# MCU.net
KiCad netlist of a schematic drawn in Altium Designer
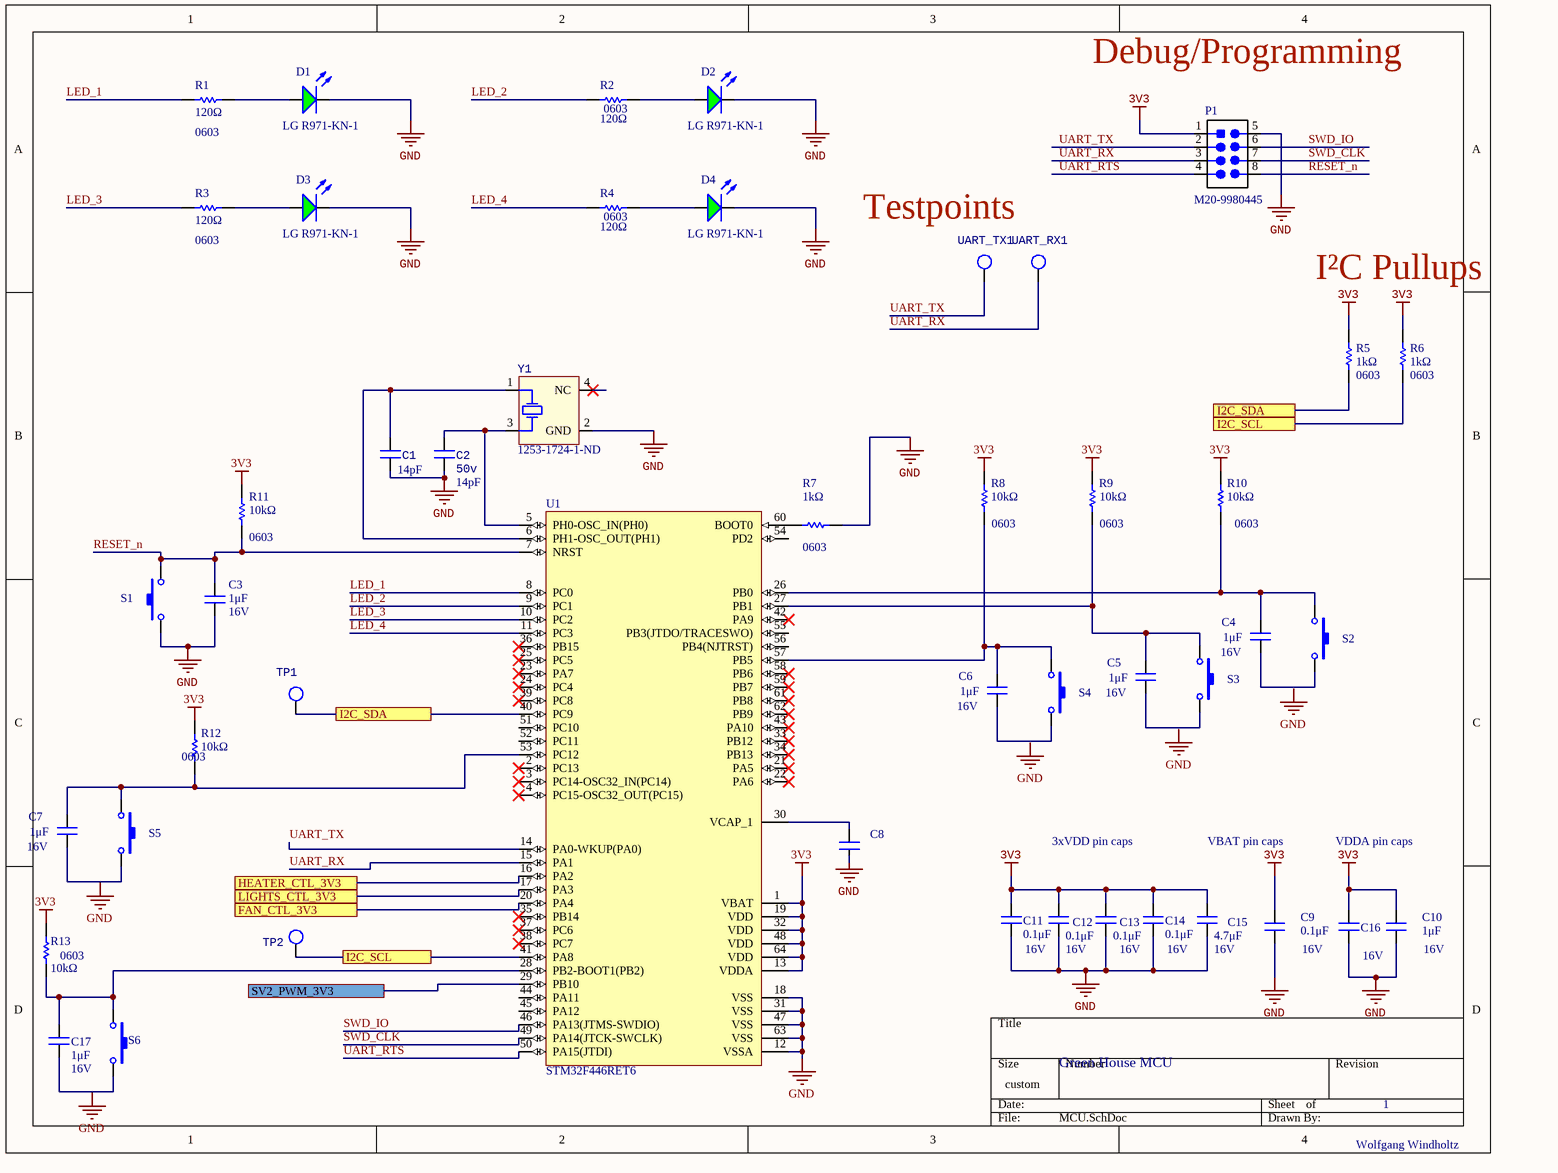
[diagram p0: MCU.SchDoc]

(export (version "E")
  (design (tool "Eeschema 10.0.6"))
  (components
    (comp (ref "C1")
      (value "14pF")
      (footprint "CAP0603")
      (description "CAP CER 14PF 50V C0G/NP0 0603")
      (fields (field (name "Comment") "CAP_14pF_50V_0603"))
      (libsource (lib "UWRT_Schematic_Library_2020") (part "CAP_14pF_50V_0603"))
    )
    (comp (ref "C2")
      (value "50v")
      (footprint "CAP0603")
      (description "CAP CER 14PF 50V C0G/NP0 0603")
      (fields (field (name "ALTIUM_VALUE") "14pF"))
      (libsource (lib "UWRT_Schematic_Library_2020") (part "CAP_14pF_50V_0603"))
    )
    (comp (ref "C3")
      (value "1μF")
      (footprint "CAP2012")
      (description "CAP CER 1UF 16V X7R 0805")
      (fields (field (name "VOLTAGE RATING") "16V") (field (name "Comment") "CAP_1uF_16V_0805"))
      (libsource (lib "UWRT_Schematic_Library_2020") (part "CAP_1uF_16V_0805"))
    )
    (comp (ref "C4")
      (value "1μF")
      (footprint "CAP2012")
      (description "CAP CER 1UF 16V X7R 0805")
      (fields (field (name "VOLTAGE RATING") "16V") (field (name "Comment") "CAP_1uF_16V_0805"))
      (libsource (lib "UWRT_Schematic_Library_2020") (part "CAP_1uF_16V_0805"))
    )
    (comp (ref "C5")
      (value "1μF")
      (footprint "CAP2012")
      (description "CAP CER 1UF 16V X7R 0805")
      (fields (field (name "VOLTAGE RATING") "16V") (field (name "Comment") "CAP_1uF_16V_0805"))
      (libsource (lib "UWRT_Schematic_Library_2020") (part "CAP_1uF_16V_0805"))
    )
    (comp (ref "C6")
      (value "1μF")
      (footprint "CAP2012")
      (description "CAP CER 1UF 16V X7R 0805")
      (fields (field (name "VOLTAGE RATING") "16V") (field (name "Comment") "CAP_1uF_16V_0805"))
      (libsource (lib "UWRT_Schematic_Library_2020") (part "CAP_1uF_16V_0805"))
    )
    (comp (ref "C7")
      (value "1μF")
      (footprint "CAP2012")
      (description "CAP CER 1UF 16V X7R 0805")
      (fields (field (name "VOLTAGE RATING") "16V") (field (name "Comment") "CAP_1uF_16V_0805"))
      (libsource (lib "UWRT_Schematic_Library_2020") (part "CAP_1uF_16V_0805"))
    )
    (comp (ref "C8")
      (value "CAP_4.7uF_50V_1206")
      (footprint "CAP1206")
      (description "CAP CER 4.7UF 50V X7R 1206")
      (libsource (lib "UWRT_Schematic_Library_2020") (part "CAP_4.7uF_50V_1206"))
    )
    (comp (ref "C9")
      (value "0.1μF")
      (footprint "CAP0603")
      (description "CAP CER 0.1UF 16V X7R 0603")
      (fields (field (name "VOLTAGE RATING") "16V") (field (name "Comment") "CAP_0.1uF_16V_0603"))
      (libsource (lib "UWRT_Schematic_Library_2020") (part "CAP_0.1uF_16V_0603"))
    )
    (comp (ref "C10")
      (value "1μF")
      (footprint "CAP0603")
      (description "CAP CER 1UF 16V Y5V 0603")
      (fields (field (name "VOLTAGE RATING") "16V") (field (name "Comment") "CAP_1uF_16V_0603"))
      (libsource (lib "UWRT_Schematic_Library_2020") (part "CAP_1uF_16V_0603"))
    )
    (comp (ref "C11")
      (value "0.1μF")
      (footprint "CAP0603")
      (description "CAP CER 0.1UF 16V X7R 0603")
      (fields (field (name "VOLTAGE RATING") "16V") (field (name "Comment") "CAP_0.1uF_16V_0603"))
      (libsource (lib "UWRT_Schematic_Library_2020") (part "CAP_0.1uF_16V_0603"))
    )
    (comp (ref "C12")
      (value "0.1μF")
      (footprint "CAP0603")
      (description "CAP CER 0.1UF 16V X7R 0603")
      (fields (field (name "VOLTAGE RATING") "16V") (field (name "Comment") "CAP_0.1uF_16V_0603"))
      (libsource (lib "UWRT_Schematic_Library_2020") (part "CAP_0.1uF_16V_0603"))
    )
    (comp (ref "C13")
      (value "0.1μF")
      (footprint "CAP0603")
      (description "CAP CER 0.1UF 16V X7R 0603")
      (fields (field (name "VOLTAGE RATING") "16V") (field (name "Comment") "CAP_0.1uF_16V_0603"))
      (libsource (lib "UWRT_Schematic_Library_2020") (part "CAP_0.1uF_16V_0603"))
    )
    (comp (ref "C14")
      (value "0.1μF")
      (footprint "CAP0603")
      (description "CAP CER 0.1UF 16V X7R 0603")
      (fields (field (name "VOLTAGE RATING") "16V") (field (name "Comment") "CAP_0.1uF_16V_0603"))
      (libsource (lib "UWRT_Schematic_Library_2020") (part "CAP_0.1uF_16V_0603"))
    )
    (comp (ref "C15")
      (value "4.7μF")
      (footprint "CAP0603")
      (description "CAP CER 4.7UF 16V X6S 0603")
      (fields (field (name "VOLTAGE RATING") "16V") (field (name "Comment") "CAP_4.7uF_16V_0603"))
      (libsource (lib "UWRT_Schematic_Library_2020") (part "CAP_4.7uF_16V_0603"))
    )
    (comp (ref "C16")
      (value "CAP_10nF_16V_0805")
      (footprint "CAP2012")
      (description "CAP CER 10000PF 16V X7R 0805")
      (fields (field (name "VOLTAGE RATING") "16V"))
      (libsource (lib "UWRT_Schematic_Library_2020") (part "CAP_10nF_16V_0805"))
    )
    (comp (ref "C17")
      (value "1μF")
      (footprint "CAP2012")
      (description "CAP CER 1UF 16V X7R 0805")
      (fields (field (name "VOLTAGE RATING") "16V") (field (name "Comment") "CAP_1uF_16V_0805"))
      (libsource (lib "UWRT_Schematic_Library_2020") (part "CAP_1uF_16V_0805"))
    )
    (comp (ref "D1")
      (value "LED_GREEN")
      (footprint "LED_0805_GREEN")
      (description "LED GREEN DIFFUSED 0805 SMD")
      (fields (field (name "MANUFACTURER PART NUMBER 1") "LG R971-KN-1"))
      (libsource (lib "UWRT_Schematic_Library_2020") (part "LED_GREEN"))
    )
    (comp (ref "D2")
      (value "LED_GREEN")
      (footprint "LED_0805_GREEN")
      (description "LED GREEN DIFFUSED 0805 SMD")
      (fields (field (name "MANUFACTURER PART NUMBER 1") "LG R971-KN-1"))
      (libsource (lib "UWRT_Schematic_Library_2020") (part "LED_GREEN"))
    )
    (comp (ref "D3")
      (value "LED_GREEN")
      (footprint "LED_0805_GREEN")
      (description "LED GREEN DIFFUSED 0805 SMD")
      (fields (field (name "MANUFACTURER PART NUMBER 1") "LG R971-KN-1"))
      (libsource (lib "UWRT_Schematic_Library_2020") (part "LED_GREEN"))
    )
    (comp (ref "D4")
      (value "LED_GREEN")
      (footprint "LED_0805_GREEN")
      (description "LED GREEN DIFFUSED 0805 SMD")
      (fields (field (name "MANUFACTURER PART NUMBER 1") "LG R971-KN-1"))
      (libsource (lib "UWRT_Schematic_Library_2020") (part "LED_GREEN"))
    )
    (comp (ref "P1")
      (value "HEADER 4X2")
      (footprint "HEADER_2X4")
      (description "CONN HEADER VERT 8POS 2.54MM")
      (fields (field (name "MANUFACTURER PART NUMBER 1") "M20-9980445"))
      (libsource (lib "UWRT_Schematic_Library_2020") (part "HEADER 4X2"))
    )
    (comp (ref "R1")
      (value "120Ω")
      (footprint "RESC0603")
      (description "RES 120 OHM 5% 1/10W 0603")
      (fields (field (name "PACKAGE/FOOTPRINT") "0603") (field (name "Comment") "RES_120Ω_0603_5%"))
      (libsource (lib "UWRT_Schematic_Library_2020") (part "RES_120Ω_0603_5%"))
    )
    (comp (ref "R2")
      (value "120Ω")
      (footprint "RESC0603")
      (description "RES 120 OHM 5% 1/10W 0603")
      (fields (field (name "PACKAGE/FOOTPRINT") "0603") (field (name "Comment") "RES_120Ω_0603_5%"))
      (libsource (lib "UWRT_Schematic_Library_2020") (part "RES_120Ω_0603_5%"))
    )
    (comp (ref "R3")
      (value "120Ω")
      (footprint "RESC0603")
      (description "RES 120 OHM 5% 1/10W 0603")
      (fields (field (name "PACKAGE/FOOTPRINT") "0603") (field (name "Comment") "RES_120Ω_0603_5%"))
      (libsource (lib "UWRT_Schematic_Library_2020") (part "RES_120Ω_0603_5%"))
    )
    (comp (ref "R4")
      (value "120Ω")
      (footprint "RESC0603")
      (description "RES 120 OHM 5% 1/10W 0603")
      (fields (field (name "PACKAGE/FOOTPRINT") "0603") (field (name "Comment") "RES_120Ω_0603_5%"))
      (libsource (lib "UWRT_Schematic_Library_2020") (part "RES_120Ω_0603_5%"))
    )
    (comp (ref "R5")
      (value "1kΩ")
      (footprint "RESC0603")
      (description "RES 1K OHM 5% 1/10W 0603")
      (fields (field (name "PACKAGE/FOOTPRINT") "0603") (field (name "Comment") "RES_1kΩ_0603_5%"))
      (libsource (lib "UWRT_Schematic_Library_2020") (part "RES_1kΩ_0603_5%"))
    )
    (comp (ref "R6")
      (value "1kΩ")
      (footprint "RESC0603")
      (description "RES 1K OHM 5% 1/10W 0603")
      (fields (field (name "PACKAGE/FOOTPRINT") "0603") (field (name "Comment") "RES_1kΩ_0603_5%"))
      (libsource (lib "UWRT_Schematic_Library_2020") (part "RES_1kΩ_0603_5%"))
    )
    (comp (ref "R7")
      (value "1kΩ")
      (footprint "RESC0603")
      (description "RES 1K OHM 5% 1/10W 0603")
      (fields (field (name "PACKAGE/FOOTPRINT") "0603") (field (name "Comment") "RES_1kΩ_0603_5%"))
      (libsource (lib "UWRT_Schematic_Library_2020") (part "RES_1kΩ_0603_5%"))
    )
    (comp (ref "R8")
      (value "10kΩ")
      (footprint "RESC0603")
      (description "RES 10K OHM 5% 1/10W 0603")
      (fields (field (name "PACKAGE/FOOTPRINT") "0603") (field (name "Comment") "RES_10kΩ_0603_5%"))
      (libsource (lib "UWRT_Schematic_Library_2020") (part "RES_10kΩ_0603_5%"))
    )
    (comp (ref "R9")
      (value "10kΩ")
      (footprint "RESC0603")
      (description "RES 10K OHM 5% 1/10W 0603")
      (fields (field (name "PACKAGE/FOOTPRINT") "0603") (field (name "Comment") "RES_10kΩ_0603_5%"))
      (libsource (lib "UWRT_Schematic_Library_2020") (part "RES_10kΩ_0603_5%"))
    )
    (comp (ref "R10")
      (value "10kΩ")
      (footprint "RESC0603")
      (description "RES 10K OHM 5% 1/10W 0603")
      (fields (field (name "PACKAGE/FOOTPRINT") "0603") (field (name "Comment") "RES_10kΩ_0603_5%"))
      (libsource (lib "UWRT_Schematic_Library_2020") (part "RES_10kΩ_0603_5%"))
    )
    (comp (ref "R11")
      (value "10kΩ")
      (footprint "RESC0603")
      (description "RES 10K OHM 5% 1/10W 0603")
      (fields (field (name "PACKAGE/FOOTPRINT") "0603") (field (name "Comment") "RES_10kΩ_0603_5%"))
      (libsource (lib "UWRT_Schematic_Library_2020") (part "RES_10kΩ_0603_5%"))
    )
    (comp (ref "R12")
      (value "10kΩ")
      (footprint "RESC0603")
      (description "RES 10K OHM 5% 1/10W 0603")
      (fields (field (name "PACKAGE/FOOTPRINT") "0603") (field (name "Comment") "RES_10kΩ_0603_5%"))
      (libsource (lib "UWRT_Schematic_Library_2020") (part "RES_10kΩ_0603_5%"))
    )
    (comp (ref "R13")
      (value "10kΩ")
      (footprint "RESC0603")
      (description "RES 10K OHM 5% 1/10W 0603")
      (fields (field (name "PACKAGE/FOOTPRINT") "0603") (field (name "Comment") "RES_10kΩ_0603_5%"))
      (libsource (lib "UWRT_Schematic_Library_2020") (part "RES_10kΩ_0603_5%"))
    )
    (comp (ref "S1")
      (value "SW_TACTILE")
      (footprint "B3U-1000P")
      (description "Tactile Switch (Grey)")
      (libsource (lib "UWRT_Schematic_Library_2020") (part "SW_TACTILE"))
    )
    (comp (ref "S2")
      (value "SW_TACTILE")
      (footprint "B3U-1000P")
      (description "Tactile Switch (Grey)")
      (libsource (lib "UWRT_Schematic_Library_2020") (part "SW_TACTILE"))
    )
    (comp (ref "S3")
      (value "SW_TACTILE")
      (footprint "B3U-1000P")
      (description "Tactile Switch (Grey)")
      (libsource (lib "UWRT_Schematic_Library_2020") (part "SW_TACTILE"))
    )
    (comp (ref "S4")
      (value "SW_TACTILE")
      (footprint "B3U-1000P")
      (description "Tactile Switch (Grey)")
      (libsource (lib "UWRT_Schematic_Library_2020") (part "SW_TACTILE"))
    )
    (comp (ref "S5")
      (value "SW_TACTILE")
      (footprint "B3U-1000P")
      (description "Tactile Switch (Grey)")
      (libsource (lib "UWRT_Schematic_Library_2020") (part "SW_TACTILE"))
    )
    (comp (ref "S6")
      (value "SW_TACTILE")
      (footprint "B3U-1000P")
      (description "Tactile Switch (Grey)")
      (libsource (lib "UWRT_Schematic_Library_2020") (part "SW_TACTILE"))
    )
    (comp (ref "TP1")
      (value "TESTPOINT_LOOP")
      (footprint "TESTPOINT_LOOP")
      (description "TESTPOINT THRUHOLE")
      (libsource (lib "UWRT_Schematic_Library_2020") (part "TESTPOINT_LOOP"))
    )
    (comp (ref "TP2")
      (value "TESTPOINT_LOOP")
      (footprint "TESTPOINT_LOOP")
      (description "TESTPOINT THRUHOLE")
      (libsource (lib "UWRT_Schematic_Library_2020") (part "TESTPOINT_LOOP"))
    )
    (comp (ref "U1")
      (value "STM32F446RET6")
      (footprint "STM-LQFP64_L")
      (libsource (lib "UWRT_Schematic_Library_2020") (part "MCU_STM32F446RET6"))
    )
    (comp (ref "UART_RX1")
      (value "TESTPOINT_LOOP")
      (footprint "TESTPOINT_LOOP")
      (description "TESTPOINT THRUHOLE")
      (libsource (lib "UWRT_Schematic_Library_2020") (part "TESTPOINT_LOOP"))
    )
    (comp (ref "UART_TX1")
      (value "TESTPOINT_LOOP")
      (footprint "TESTPOINT_LOOP")
      (description "TESTPOINT THRUHOLE")
      (libsource (lib "UWRT_Schematic_Library_2020") (part "TESTPOINT_LOOP"))
    )
    (comp (ref "Y1")
      (value "CRYSTAL_25MHZ")
      (footprint "SOIC254P1016X440-4N")
      (description "CRYSTAL 25.0000MHZ 12PF SMD")
      (fields (field (name "SUPPLIER PART NUMBER 1") "1253-1724-1-ND"))
      (libsource (lib "UWRT_Schematic_Library_2020") (part "CRYSTAL_25MHZ"))
    )
  )
  (nets
    (net (code "1") (name "/FAN_CTL_3V3") (class "Default")
      (node (ref "U1") (pin "20") (pinfunction "PA4_20") (pintype "bidirectional"))
    )
    (net (code "2") (name "/HEATER_CTL_3V3") (class "Default")
      (node (ref "U1") (pin "16") (pinfunction "PA2_16") (pintype "bidirectional"))
    )
    (net (code "3") (name "/I2C_SCL") (class "Default")
      (node (ref "R6") (pin "1") (pinfunction "1_1") (pintype "passive"))
      (node (ref "TP2") (pin "1") (pintype "passive"))
      (node (ref "U1") (pin "41") (pinfunction "PA8_41") (pintype "bidirectional"))
    )
    (net (code "4") (name "/I2C_SDA") (class "Default")
      (node (ref "R5") (pin "1") (pinfunction "1_1") (pintype "passive"))
      (node (ref "TP1") (pin "1") (pintype "passive"))
      (node (ref "U1") (pin "40") (pinfunction "PC9_40") (pintype "bidirectional"))
    )
    (net (code "5") (name "/LED_1") (class "Default")
      (node (ref "R1") (pin "1") (pinfunction "1_1") (pintype "passive"))
      (node (ref "U1") (pin "8") (pinfunction "PC0_8") (pintype "bidirectional"))
    )
    (net (code "6") (name "/LED_2") (class "Default")
      (node (ref "R2") (pin "1") (pinfunction "1_1") (pintype "passive"))
      (node (ref "U1") (pin "9") (pinfunction "PC1_9") (pintype "bidirectional"))
    )
    (net (code "7") (name "/LED_3") (class "Default")
      (node (ref "R3") (pin "1") (pinfunction "1_1") (pintype "passive"))
      (node (ref "U1") (pin "10") (pinfunction "PC2_10") (pintype "bidirectional"))
    )
    (net (code "8") (name "/LED_4") (class "Default")
      (node (ref "R4") (pin "1") (pinfunction "1_1") (pintype "passive"))
      (node (ref "U1") (pin "11") (pinfunction "PC3_11") (pintype "bidirectional"))
    )
    (net (code "9") (name "/LIGHTS_CTL_3V3") (class "Default")
      (node (ref "U1") (pin "17") (pinfunction "PA3_17") (pintype "bidirectional"))
    )
    (net (code "10") (name "/RESET_n") (class "Default")
      (node (ref "C3") (pin "2") (pinfunction "2_2") (pintype "passive"))
      (node (ref "P1") (pin "8") (pinfunction "4_8") (pintype "passive"))
      (node (ref "R11") (pin "1") (pinfunction "1_1") (pintype "passive"))
      (node (ref "S1") (pin "1") (pinfunction "1_1") (pintype "passive"))
      (node (ref "U1") (pin "7") (pinfunction "NRST_7") (pintype "bidirectional"))
    )
    (net (code "11") (name "/SV2_PWM_3V3") (class "Default")
      (node (ref "U1") (pin "29") (pinfunction "PB10_29") (pintype "bidirectional"))
    )
    (net (code "12") (name "/SWD_CLK") (class "Default")
      (node (ref "P1") (pin "7") (pinfunction "3_7") (pintype "passive"))
      (node (ref "U1") (pin "49") (pinfunction "PA14(JTCK-SWCLK)_49") (pintype "bidirectional"))
    )
    (net (code "13") (name "/SWD_IO") (class "Default")
      (node (ref "P1") (pin "6") (pinfunction "2_6") (pintype "passive"))
      (node (ref "U1") (pin "46") (pinfunction "PA13(JTMS-SWDIO)_46") (pintype "bidirectional"))
    )
    (net (code "14") (name "/UART_RTS") (class "Default")
      (node (ref "P1") (pin "4") (pinfunction "4_4") (pintype "passive"))
      (node (ref "U1") (pin "50") (pinfunction "PA15(JTDI)_50") (pintype "bidirectional"))
    )
    (net (code "15") (name "/UART_RX") (class "Default")
      (node (ref "P1") (pin "3") (pinfunction "3_3") (pintype "passive"))
      (node (ref "U1") (pin "15") (pinfunction "PA1_15") (pintype "bidirectional"))
      (node (ref "UART_RX1") (pin "1") (pintype "passive"))
    )
    (net (code "16") (name "/UART_TX") (class "Default")
      (node (ref "P1") (pin "2") (pinfunction "2_2") (pintype "passive"))
      (node (ref "U1") (pin "14") (pinfunction "PA0-WKUP(PA0)_14") (pintype "bidirectional"))
      (node (ref "UART_TX1") (pin "1") (pintype "passive"))
    )
    (net (code "17") (name "3V3") (class "Default")
      (node (ref "C10") (pin "2") (pinfunction "2_2") (pintype "passive"))
      (node (ref "C11") (pin "2") (pinfunction "2_2") (pintype "passive"))
      (node (ref "C12") (pin "2") (pinfunction "2_2") (pintype "passive"))
      (node (ref "C13") (pin "2") (pinfunction "2_2") (pintype "passive"))
      (node (ref "C14") (pin "2") (pinfunction "2_2") (pintype "passive"))
      (node (ref "C15") (pin "2") (pinfunction "2_2") (pintype "passive"))
      (node (ref "C16") (pin "2") (pinfunction "2_2") (pintype "passive"))
      (node (ref "C9") (pin "2") (pinfunction "2_2") (pintype "passive"))
      (node (ref "P1") (pin "1") (pinfunction "VCC_1") (pintype "passive"))
      (node (ref "R10") (pin "2") (pinfunction "2_2") (pintype "passive"))
      (node (ref "R11") (pin "2") (pinfunction "2_2") (pintype "passive"))
      (node (ref "R12") (pin "2") (pinfunction "2_2") (pintype "passive"))
      (node (ref "R13") (pin "2") (pinfunction "2_2") (pintype "passive"))
      (node (ref "R5") (pin "2") (pinfunction "2_2") (pintype "passive"))
      (node (ref "R6") (pin "2") (pinfunction "2_2") (pintype "passive"))
      (node (ref "R8") (pin "2") (pinfunction "2_2") (pintype "passive"))
      (node (ref "R9") (pin "2") (pinfunction "2_2") (pintype "passive"))
      (node (ref "U1") (pin "1") (pinfunction "VBAT_1") (pintype "power_in"))
      (node (ref "U1") (pin "13") (pinfunction "VDDA_13") (pintype "power_in"))
      (node (ref "U1") (pin "19") (pinfunction "VDD_19") (pintype "power_in"))
      (node (ref "U1") (pin "32") (pinfunction "VDD_32") (pintype "power_in"))
      (node (ref "U1") (pin "48") (pinfunction "VDD_48") (pintype "power_in"))
      (node (ref "U1") (pin "64") (pinfunction "VDD_64") (pintype "power_in"))
    )
    (net (code "18") (name "GND") (class "Default")
      (node (ref "C1") (pin "1") (pinfunction "1_1") (pintype "passive"))
      (node (ref "C10") (pin "1") (pinfunction "1_1") (pintype "passive"))
      (node (ref "C11") (pin "1") (pinfunction "1_1") (pintype "passive"))
      (node (ref "C12") (pin "1") (pinfunction "1_1") (pintype "passive"))
      (node (ref "C13") (pin "1") (pinfunction "1_1") (pintype "passive"))
      (node (ref "C14") (pin "1") (pinfunction "1_1") (pintype "passive"))
      (node (ref "C15") (pin "1") (pinfunction "1_1") (pintype "passive"))
      (node (ref "C16") (pin "1") (pinfunction "1_1") (pintype "passive"))
      (node (ref "C2") (pin "1") (pinfunction "1_1") (pintype "passive"))
      (node (ref "C3") (pin "1") (pinfunction "1_1") (pintype "passive"))
      (node (ref "C8") (pin "1") (pinfunction "1_1") (pintype "passive"))
      (node (ref "C9") (pin "1") (pinfunction "1_1") (pintype "passive"))
      (node (ref "D1") (pin "2") (pinfunction "K_2") (pintype "passive"))
      (node (ref "D2") (pin "2") (pinfunction "K_2") (pintype "passive"))
      (node (ref "D3") (pin "2") (pinfunction "K_2") (pintype "passive"))
      (node (ref "D4") (pin "2") (pinfunction "K_2") (pintype "passive"))
      (node (ref "P1") (pin "5") (pinfunction "GND_5") (pintype "passive"))
      (node (ref "R7") (pin "2") (pinfunction "2_2") (pintype "passive"))
      (node (ref "S1") (pin "2") (pinfunction "2_2") (pintype "passive"))
      (node (ref "U1") (pin "12") (pinfunction "VSSA_12") (pintype "power_in"))
      (node (ref "U1") (pin "18") (pinfunction "VSS_18") (pintype "power_in"))
      (node (ref "U1") (pin "31") (pinfunction "VSS_31") (pintype "power_in"))
      (node (ref "U1") (pin "47") (pinfunction "VSS_47") (pintype "power_in"))
      (node (ref "U1") (pin "63") (pinfunction "VSS_63") (pintype "power_in"))
      (node (ref "Y1") (pin "2") (pinfunction "GND_2") (pintype "power_in"))
    )
    (net (code "19") (name "Net-(C4-Pad1)") (class "Default")
      (node (ref "C4") (pin "1") (pinfunction "1_1") (pintype "passive"))
      (node (ref "S2") (pin "2") (pinfunction "2_2") (pintype "passive"))
    )
    (net (code "20") (name "Net-(C5-Pad1)") (class "Default")
      (node (ref "C5") (pin "1") (pinfunction "1_1") (pintype "passive"))
      (node (ref "S3") (pin "2") (pinfunction "2_2") (pintype "passive"))
    )
    (net (code "21") (name "Net-(C6-Pad1)") (class "Default")
      (node (ref "C6") (pin "1") (pinfunction "1_1") (pintype "passive"))
      (node (ref "S4") (pin "2") (pinfunction "2_2") (pintype "passive"))
    )
    (net (code "22") (name "Net-(C7-Pad1)") (class "Default")
      (node (ref "C7") (pin "1") (pinfunction "1_1") (pintype "passive"))
      (node (ref "S5") (pin "2") (pinfunction "2_2") (pintype "passive"))
    )
    (net (code "23") (name "Net-(C17-Pad1)") (class "Default")
      (node (ref "C17") (pin "1") (pinfunction "1_1") (pintype "passive"))
      (node (ref "S6") (pin "2") (pinfunction "2_2") (pintype "passive"))
    )
    (net (code "24") (name "Net-(D1-A)") (class "Default")
      (node (ref "D1") (pin "1") (pinfunction "A_1") (pintype "passive"))
      (node (ref "R1") (pin "2") (pinfunction "2_2") (pintype "passive"))
    )
    (net (code "25") (name "Net-(D2-A)") (class "Default")
      (node (ref "D2") (pin "1") (pinfunction "A_1") (pintype "passive"))
      (node (ref "R2") (pin "2") (pinfunction "2_2") (pintype "passive"))
    )
    (net (code "26") (name "Net-(D3-A)") (class "Default")
      (node (ref "D3") (pin "1") (pinfunction "A_1") (pintype "passive"))
      (node (ref "R3") (pin "2") (pinfunction "2_2") (pintype "passive"))
    )
    (net (code "27") (name "Net-(D4-A)") (class "Default")
      (node (ref "D4") (pin "1") (pinfunction "A_1") (pintype "passive"))
      (node (ref "R4") (pin "2") (pinfunction "2_2") (pintype "passive"))
    )
    (net (code "28") (name "Net-(U1-BOOT0)") (class "Default")
      (node (ref "R7") (pin "1") (pinfunction "1_1") (pintype "passive"))
      (node (ref "U1") (pin "60") (pinfunction "BOOT0_60") (pintype "input"))
    )
    (net (code "29") (name "Net-(U1-PB0)") (class "Default")
      (node (ref "C4") (pin "2") (pinfunction "2_2") (pintype "passive"))
      (node (ref "R10") (pin "1") (pinfunction "1_1") (pintype "passive"))
      (node (ref "S2") (pin "1") (pinfunction "1_1") (pintype "passive"))
      (node (ref "U1") (pin "26") (pinfunction "PB0_26") (pintype "bidirectional"))
    )
    (net (code "30") (name "Net-(U1-PB1)") (class "Default")
      (node (ref "C5") (pin "2") (pinfunction "2_2") (pintype "passive"))
      (node (ref "R9") (pin "1") (pinfunction "1_1") (pintype "passive"))
      (node (ref "S3") (pin "1") (pinfunction "1_1") (pintype "passive"))
      (node (ref "U1") (pin "27") (pinfunction "PB1_27") (pintype "bidirectional"))
    )
    (net (code "31") (name "Net-(U1-PB2-BOOT1(PB2))") (class "Default")
      (node (ref "C17") (pin "2") (pinfunction "2_2") (pintype "passive"))
      (node (ref "R13") (pin "1") (pinfunction "1_1") (pintype "passive"))
      (node (ref "S6") (pin "1") (pinfunction "1_1") (pintype "passive"))
      (node (ref "U1") (pin "28") (pinfunction "PB2-BOOT1(PB2)_28") (pintype "bidirectional"))
    )
    (net (code "32") (name "Net-(U1-PB5)") (class "Default")
      (node (ref "C6") (pin "2") (pinfunction "2_2") (pintype "passive"))
      (node (ref "R8") (pin "1") (pinfunction "1_1") (pintype "passive"))
      (node (ref "S4") (pin "1") (pinfunction "1_1") (pintype "passive"))
      (node (ref "U1") (pin "57") (pinfunction "PB5_57") (pintype "bidirectional"))
    )
    (net (code "33") (name "Net-(U1-PC12)") (class "Default")
      (node (ref "C7") (pin "2") (pinfunction "2_2") (pintype "passive"))
      (node (ref "R12") (pin "1") (pinfunction "1_1") (pintype "passive"))
      (node (ref "S5") (pin "1") (pinfunction "1_1") (pintype "passive"))
      (node (ref "U1") (pin "53") (pinfunction "PC12_53") (pintype "bidirectional"))
    )
    (net (code "34") (name "Net-(U1-PH0-OSC_IN(PH0))") (class "Default")
      (node (ref "C2") (pin "2") (pinfunction "2_2") (pintype "passive"))
      (node (ref "U1") (pin "5") (pinfunction "PH0-OSC_IN(PH0)_5") (pintype "bidirectional"))
      (node (ref "Y1") (pin "3") (pinfunction "HOT_3") (pintype "passive"))
    )
    (net (code "35") (name "Net-(U1-PH1-OSC_OUT(PH1))") (class "Default")
      (node (ref "C1") (pin "2") (pinfunction "2_2") (pintype "passive"))
      (node (ref "U1") (pin "6") (pinfunction "PH1-OSC_OUT(PH1)_6") (pintype "bidirectional"))
      (node (ref "Y1") (pin "1") (pinfunction "HOT_1") (pintype "passive"))
    )
    (net (code "36") (name "Net-(U1-VCAP_1)") (class "Default")
      (node (ref "C8") (pin "2") (pinfunction "2_2") (pintype "passive"))
      (node (ref "U1") (pin "30") (pinfunction "VCAP_1_30") (pintype "passive"))
    )
    (net (code "37") (name "unconnected-(U1-PA5-Pad21)") (class "Default")
      (node (ref "U1") (pin "21") (pinfunction "PA5_21") (pintype "bidirectional+no_connect"))
    )
    (net (code "38") (name "unconnected-(U1-PA6-Pad22)") (class "Default")
      (node (ref "U1") (pin "22") (pinfunction "PA6_22") (pintype "bidirectional+no_connect"))
    )
    (net (code "39") (name "unconnected-(U1-PA7-Pad23)") (class "Default")
      (node (ref "U1") (pin "23") (pinfunction "PA7_23") (pintype "bidirectional+no_connect"))
    )
    (net (code "40") (name "unconnected-(U1-PA9-Pad42)") (class "Default")
      (node (ref "U1") (pin "42") (pinfunction "PA9_42") (pintype "bidirectional+no_connect"))
    )
    (net (code "41") (name "unconnected-(U1-PA10-Pad43)") (class "Default")
      (node (ref "U1") (pin "43") (pinfunction "PA10_43") (pintype "bidirectional+no_connect"))
    )
    (net (code "42") (name "unconnected-(U1-PA11-Pad44)") (class "Default")
      (node (ref "U1") (pin "44") (pinfunction "PA11_44") (pintype "bidirectional"))
    )
    (net (code "43") (name "unconnected-(U1-PA12-Pad45)") (class "Default")
      (node (ref "U1") (pin "45") (pinfunction "PA12_45") (pintype "bidirectional"))
    )
    (net (code "44") (name "unconnected-(U1-PB3(JTDO{slash}TRACESWO)-Pad55)") (class "Default")
      (node (ref "U1") (pin "55") (pinfunction "PB3(JTDO/TRACESWO)_55") (pintype "bidirectional"))
    )
    (net (code "45") (name "unconnected-(U1-PB4(NJTRST)-Pad56)") (class "Default")
      (node (ref "U1") (pin "56") (pinfunction "PB4(NJTRST)_56") (pintype "bidirectional"))
    )
    (net (code "46") (name "unconnected-(U1-PB6-Pad58)") (class "Default")
      (node (ref "U1") (pin "58") (pinfunction "PB6_58") (pintype "bidirectional+no_connect"))
    )
    (net (code "47") (name "unconnected-(U1-PB7-Pad59)") (class "Default")
      (node (ref "U1") (pin "59") (pinfunction "PB7_59") (pintype "bidirectional+no_connect"))
    )
    (net (code "48") (name "unconnected-(U1-PB8-Pad61)") (class "Default")
      (node (ref "U1") (pin "61") (pinfunction "PB8_61") (pintype "bidirectional+no_connect"))
    )
    (net (code "49") (name "unconnected-(U1-PB9-Pad62)") (class "Default")
      (node (ref "U1") (pin "62") (pinfunction "PB9_62") (pintype "bidirectional+no_connect"))
    )
    (net (code "50") (name "unconnected-(U1-PB12-Pad33)") (class "Default")
      (node (ref "U1") (pin "33") (pinfunction "PB12_33") (pintype "bidirectional+no_connect"))
    )
    (net (code "51") (name "unconnected-(U1-PB13-Pad34)") (class "Default")
      (node (ref "U1") (pin "34") (pinfunction "PB13_34") (pintype "bidirectional+no_connect"))
    )
    (net (code "52") (name "unconnected-(U1-PB14-Pad35)") (class "Default")
      (node (ref "U1") (pin "35") (pinfunction "PB14_35") (pintype "bidirectional+no_connect"))
    )
    (net (code "53") (name "unconnected-(U1-PB15-Pad36)") (class "Default")
      (node (ref "U1") (pin "36") (pinfunction "PB15_36") (pintype "bidirectional+no_connect"))
    )
    (net (code "54") (name "unconnected-(U1-PC4-Pad24)") (class "Default")
      (node (ref "U1") (pin "24") (pinfunction "PC4_24") (pintype "bidirectional+no_connect"))
    )
    (net (code "55") (name "unconnected-(U1-PC5-Pad25)") (class "Default")
      (node (ref "U1") (pin "25") (pinfunction "PC5_25") (pintype "bidirectional+no_connect"))
    )
    (net (code "56") (name "unconnected-(U1-PC6-Pad37)") (class "Default")
      (node (ref "U1") (pin "37") (pinfunction "PC6_37") (pintype "bidirectional+no_connect"))
    )
    (net (code "57") (name "unconnected-(U1-PC7-Pad38)") (class "Default")
      (node (ref "U1") (pin "38") (pinfunction "PC7_38") (pintype "bidirectional+no_connect"))
    )
    (net (code "58") (name "unconnected-(U1-PC8-Pad39)") (class "Default")
      (node (ref "U1") (pin "39") (pinfunction "PC8_39") (pintype "bidirectional+no_connect"))
    )
    (net (code "59") (name "unconnected-(U1-PC10-Pad51)") (class "Default")
      (node (ref "U1") (pin "51") (pinfunction "PC10_51") (pintype "bidirectional"))
    )
    (net (code "60") (name "unconnected-(U1-PC11-Pad52)") (class "Default")
      (node (ref "U1") (pin "52") (pinfunction "PC11_52") (pintype "bidirectional"))
    )
    (net (code "61") (name "unconnected-(U1-PC13-Pad2)") (class "Default")
      (node (ref "U1") (pin "2") (pinfunction "PC13_2") (pintype "bidirectional+no_connect"))
    )
    (net (code "62") (name "unconnected-(U1-PC14-OSC32_IN(PC14)-Pad3)") (class "Default")
      (node (ref "U1") (pin "3") (pinfunction "PC14-OSC32_IN(PC14)_3") (pintype "bidirectional+no_connect"))
    )
    (net (code "63") (name "unconnected-(U1-PC15-OSC32_OUT(PC15)-Pad4)") (class "Default")
      (node (ref "U1") (pin "4") (pinfunction "PC15-OSC32_OUT(PC15)_4") (pintype "bidirectional+no_connect"))
    )
    (net (code "64") (name "unconnected-(U1-PD2-Pad54)") (class "Default")
      (node (ref "U1") (pin "54") (pinfunction "PD2_54") (pintype "bidirectional"))
    )
    (net (code "65") (name "unconnected-(Y1-NC-Pad4)") (class "Default")
      (node (ref "Y1") (pin "4") (pinfunction "NC_4") (pintype "passive+no_connect"))
    )
  )
)
